# Schematic.net
KiCad netlist of a schematic drawn in Altium Designer
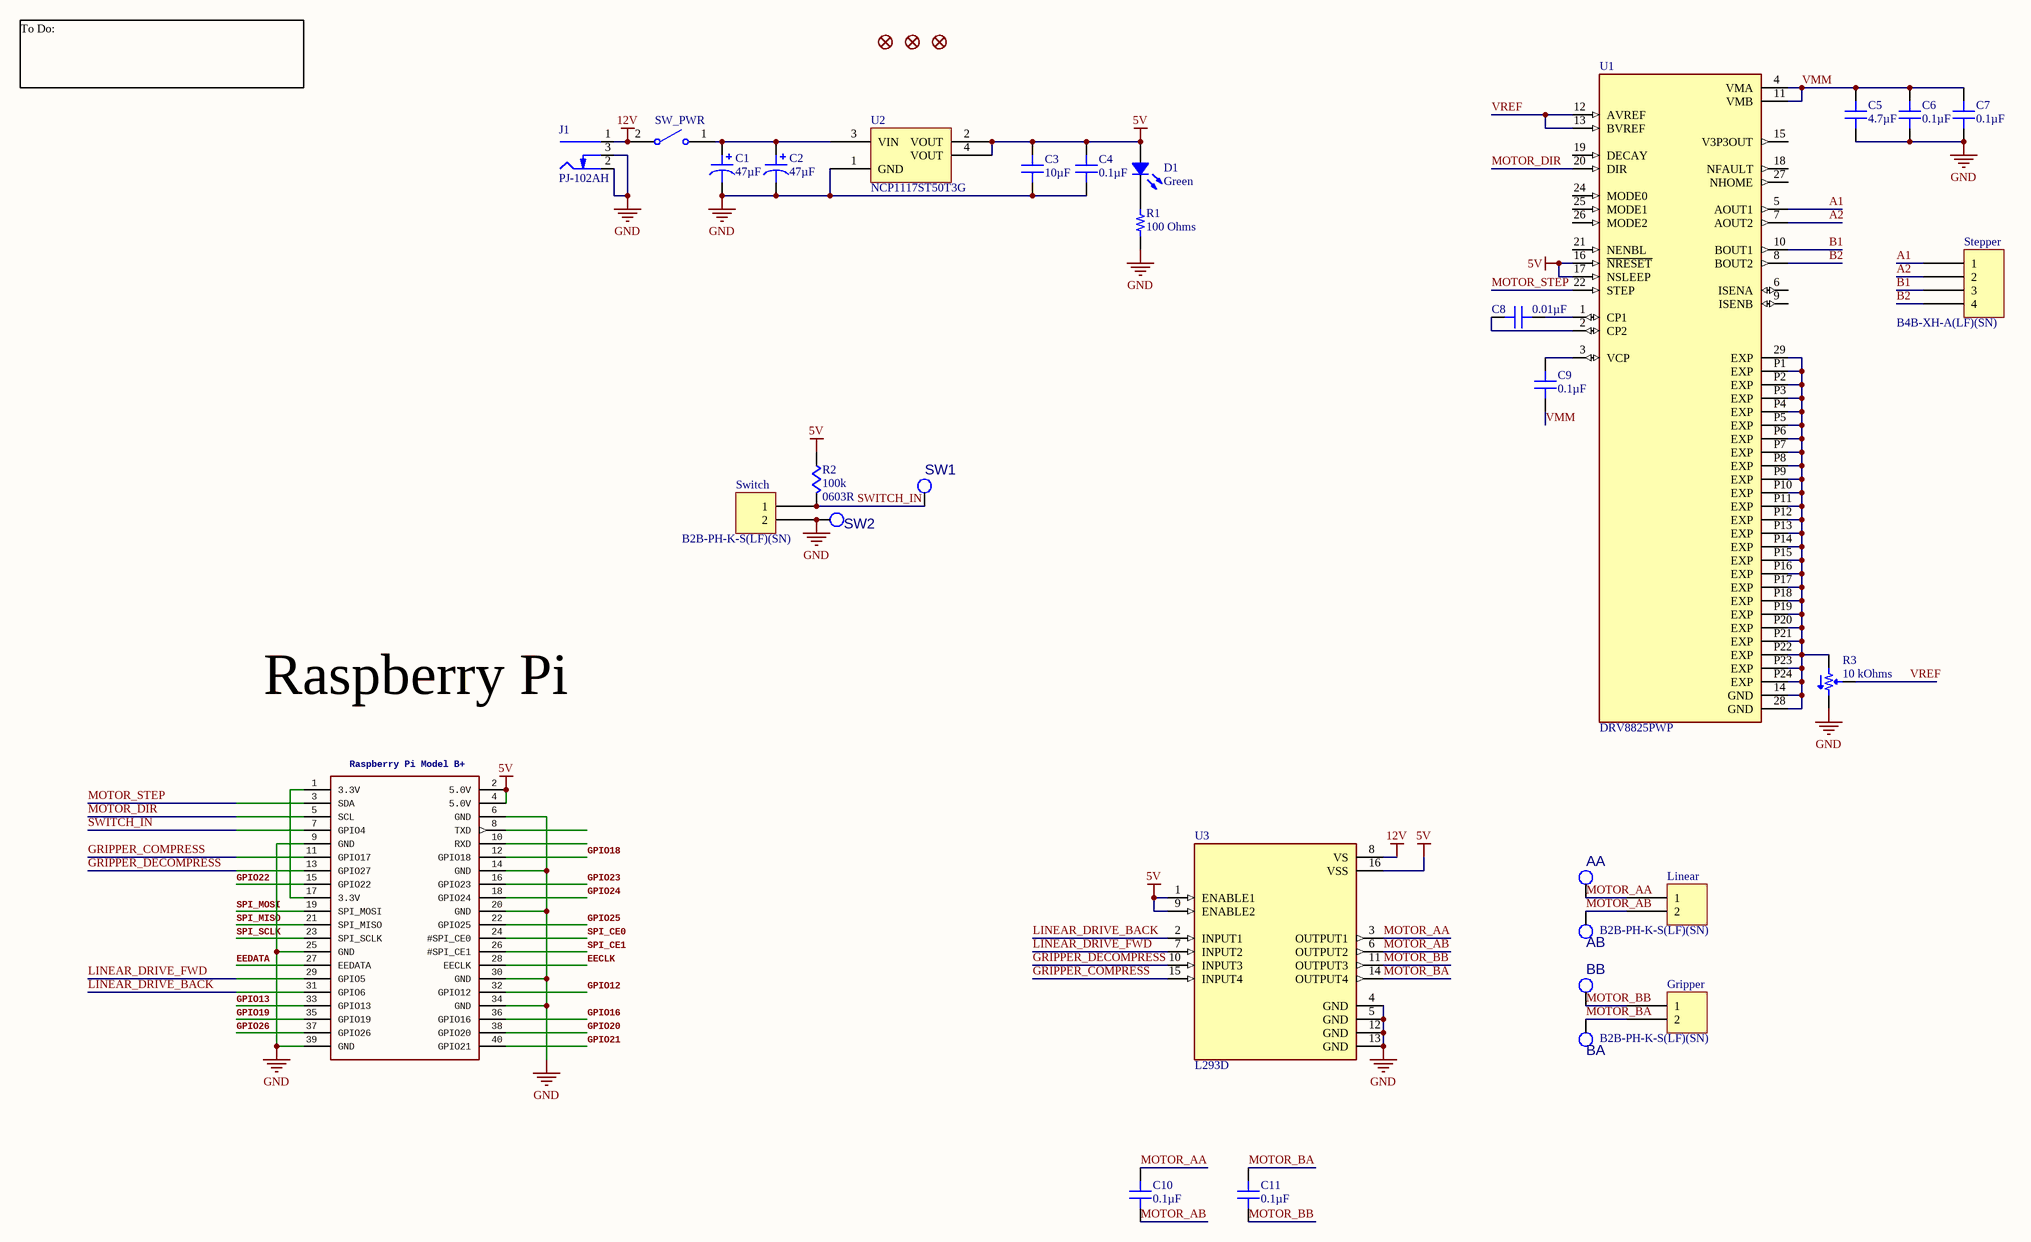
[diagram p0: Schematic.SchDoc]

(export (version "E")
  (design (tool "Eeschema 10.0.6"))
  (components
    (comp (ref "AA")
      (value "TH_Testpoint_40mil")
      (footprint "TH_Testpoint_40mil")
      (description "TH Testpoint")
      (libsource (lib "Testpoint") (part "TH_Testpoint_40mil"))
    )
    (comp (ref "AB")
      (value "TH_Testpoint_40mil")
      (footprint "TH_Testpoint_40mil")
      (description "TH Testpoint")
      (libsource (lib "Testpoint") (part "TH_Testpoint_40mil"))
    )
    (comp (ref "BA")
      (value "TH_Testpoint_40mil")
      (footprint "TH_Testpoint_40mil")
      (description "TH Testpoint")
      (libsource (lib "Testpoint") (part "TH_Testpoint_40mil"))
    )
    (comp (ref "BB")
      (value "TH_Testpoint_40mil")
      (footprint "TH_Testpoint_40mil")
      (description "TH Testpoint")
      (libsource (lib "Testpoint") (part "TH_Testpoint_40mil"))
    )
    (comp (ref "C1")
      (value "47µF")
      (footprint "CAP ALSMD 6.6MM H6.1MM")
      (description "CAP ALUM 47UF 20% 35V SMD")
      (fields (field (name "PART NUMBER") "UCD1V470MCL1GS") (field (name "MANUFACTURER") "Nichicon"))
      (libsource (lib "Celestial Altium Library - altium_library") (part "Polarised Capacitor"))
    )
    (comp (ref "C2")
      (value "47µF")
      (footprint "CAP ALSMD 6.6MM H6.1MM")
      (description "CAP ALUM 47UF 20% 35V SMD")
      (fields (field (name "PART NUMBER") "UCD1V470MCL1GS") (field (name "MANUFACTURER") "Nichicon"))
      (libsource (lib "Celestial Altium Library - altium_library") (part "Polarised Capacitor"))
    )
    (comp (ref "C3")
      (value "10µF")
      (footprint "CAP 0805_2012")
      (description "CAP CER 10UF 25V X5R 0805")
      (fields
        (field (name "PART NUMBER") "C2012X5R1E106K085AC")
        (field (name "MANUFACTURER") "TDK Corporation")
      )
      (libsource (lib "Celestial Altium Library - altium_library") (part "Capacitor"))
    )
    (comp (ref "C4")
      (value "0.1µF")
      (footprint "CAP 0603_1608")
      (description "CAP CER 0.1UF 50V X7R 0603")
      (fields
        (field (name "PART NUMBER") "CGA3E2X7R1H104K080AE")
        (field (name "MANUFACTURER") "TDK Corporation")
      )
      (libsource (lib "Celestial Altium Library - altium_library") (part "Capacitor"))
    )
    (comp (ref "C5")
      (value "4.7µF")
      (footprint "CAP 0603_1608")
      (description "CAP CER 4.7UF 35V X5R 0603")
      (fields
        (field (name "PART NUMBER") "C1608X5R1V475M080AC")
        (field (name "MANUFACTURER") "TDK Corporation")
      )
      (libsource (lib "Celestial Altium Library - altium_library") (part "Capacitor"))
    )
    (comp (ref "C6")
      (value "0.1µF")
      (footprint "CAP 0603_1608")
      (description "CAP CER 0.1UF 50V X7R 0603")
      (fields
        (field (name "PART NUMBER") "CGA3E2X7R1H104K080AE")
        (field (name "MANUFACTURER") "TDK Corporation")
      )
      (libsource (lib "Celestial Altium Library - altium_library") (part "Capacitor"))
    )
    (comp (ref "C7")
      (value "0.1µF")
      (footprint "CAP 0603_1608")
      (description "CAP CER 0.1UF 50V X7R 0603")
      (fields
        (field (name "PART NUMBER") "CGA3E2X7R1H104K080AE")
        (field (name "MANUFACTURER") "TDK Corporation")
      )
      (libsource (lib "Celestial Altium Library - altium_library") (part "Capacitor"))
    )
    (comp (ref "C8")
      (value "0.01µF")
      (footprint "CAP 0603_1608")
      (description "CAP CER 0.01UF 250V X7R 0603")
      (fields (field (name "PART NUMBER") "C0603C103KARACAUTO") (field (name "MANUFACTURER") "KEMET"))
      (libsource (lib "Celestial Altium Library - altium_library") (part "Capacitor"))
    )
    (comp (ref "C9")
      (value "0.1µF")
      (footprint "CAP 0603_1608")
      (description "CAP CER 0.1UF 50V X7R 0603")
      (fields
        (field (name "PART NUMBER") "CGA3E2X7R1H104K080AE")
        (field (name "MANUFACTURER") "TDK Corporation")
      )
      (libsource (lib "Celestial Altium Library - altium_library") (part "Capacitor"))
    )
    (comp (ref "C10")
      (value "0.1µF")
      (footprint "CAP 0603_1608")
      (description "CAP CER 0.1UF 50V X7R 0603")
      (fields
        (field (name "PART NUMBER") "CGA3E2X7R1H104K080AE")
        (field (name "MANUFACTURER") "TDK Corporation")
      )
      (libsource (lib "Celestial Altium Library - altium_library") (part "Capacitor"))
    )
    (comp (ref "C11")
      (value "0.1µF")
      (footprint "CAP 0603_1608")
      (description "CAP CER 0.1UF 50V X7R 0603")
      (fields
        (field (name "PART NUMBER") "CGA3E2X7R1H104K080AE")
        (field (name "MANUFACTURER") "TDK Corporation")
      )
      (libsource (lib "Celestial Altium Library - altium_library") (part "Capacitor"))
    )
    (comp (ref "D1")
      (value "Green")
      (footprint "LED 0603_1608 GREEN")
      (description "LED GREEN CLEAR 1608 SMD")
      (fields (field (name "PART NUMBER") "APT1608CGCK") (field (name "MANUFACTURER") "Kingbright"))
      (libsource (lib "Celestial Altium Library - altium_library") (part "LED"))
    )
    (comp (ref "FID1")
      (value "FIDUCIAL\"\"")
      (footprint "FIDUCIAL_1MM")
      (description "Fiducial Alignment PointsVarious fiducial points for machine vision alignment.")
      (libsource (lib "microbuilder") (part "FIDUCIAL{dblquote}{dblquote}"))
    )
    (comp (ref "FID2")
      (value "FIDUCIAL\"\"")
      (footprint "FIDUCIAL_1MM")
      (description "Fiducial Alignment PointsVarious fiducial points for machine vision alignment.")
      (libsource (lib "microbuilder") (part "FIDUCIAL{dblquote}{dblquote}"))
    )
    (comp (ref "FID3")
      (value "FIDUCIAL\"\"")
      (footprint "FIDUCIAL_1MM")
      (description "Fiducial Alignment PointsVarious fiducial points for machine vision alignment.")
      (libsource (lib "microbuilder") (part "FIDUCIAL{dblquote}{dblquote}"))
    )
    (comp (ref "Gripper")
      (value "B2B-PH-K-S(LF)(SN)")
      (footprint "JST B2B-PH-K")
      (description "CONN HEADER VERT 2POS 2MM")
      (fields (field (name "MANUFACTURER") "JST Sales America Inc."))
      (libsource (lib "Celestial Altium Library - altium_library") (part "2 Pin"))
    )
    (comp (ref "J1")
      (value "PJ-102AH")
      (footprint "CUI PJ-102AH")
      (description "CONN PWR JACK 2X5.5MM SOLDER")
      (fields (field (name "MANUFACTURER") "CUI Devices"))
      (libsource (lib "Celestial Altium Library - altium_library") (part "Barrel Connector"))
    )
    (comp (ref "Linear")
      (value "B2B-PH-K-S(LF)(SN)")
      (footprint "JST B2B-PH-K")
      (description "CONN HEADER VERT 2POS 2MM")
      (fields (field (name "MANUFACTURER") "JST Sales America Inc."))
      (libsource (lib "Celestial Altium Library - altium_library") (part "2 Pin"))
    )
    (comp (ref "R1")
      (value "100 Ohms")
      (footprint "RES 0603_1608")
      (description "RES 100 OHM 0.1% 1/16W 0603")
      (fields
        (field (name "PART NUMBER") "RNCS0603BKE100R")
        (field (name "MANUFACTURER") "Stackpole Electronics Inc")
      )
      (libsource (lib "Celestial Altium Library - altium_library") (part "Resistor"))
    )
    (comp (ref "R2")
      (value "100k")
      (footprint "0603R")
      (fields (field (name "Comment") "Resistor 0603"))
      (libsource (lib "MikesAltiumLibrary") (part "Resistor"))
    )
    (comp (ref "R3")
      (value "10 kOhms")
      (footprint "POT BOURNS TRIMPOT TC33")
      (description "TRIMMER 10K OHM 0.1W J LEAD TOP")
      (fields (field (name "PART NUMBER") "TC33X-2-103E") (field (name "MANUFACTURER") "Bourns Inc."))
      (libsource (lib "Celestial Altium Library - altium_library") (part "Potentiometer"))
    )
    (comp (ref "RPI1")
      (value "RASPBERRYPI_BPLUS_HATSLOTS")
      (footprint "PI_HAT_SLOTS")
      (fields (field (name "RASPBERRYPIMODELB+") "Raspberry Pi Model B+"))
      (libsource (lib "microbuilder") (part "RASPBERRYPI_BPLUS_HATSLOTS"))
    )
    (comp (ref "Stepper")
      (value "B4B-XH-A(LF)(SN)")
      (footprint "JST XH B4B-XH-A")
      (description "CONN HEADER VERT 4POS 2.5MM")
      (fields (field (name "MANUFACTURER") "JST Sales America Inc."))
      (libsource (lib "Celestial Altium Library - altium_library") (part "4 Pin"))
    )
    (comp (ref "SW1")
      (value "TH_Testpoint_40mil")
      (footprint "TH_Testpoint_40mil")
      (description "TH Testpoint")
      (libsource (lib "Testpoint") (part "TH_Testpoint_40mil"))
    )
    (comp (ref "SW2")
      (value "TH_Testpoint_40mil")
      (footprint "TH_Testpoint_40mil")
      (description "TH Testpoint")
      (libsource (lib "Testpoint") (part "TH_Testpoint_40mil"))
    )
    (comp (ref "Switch")
      (value "B2B-PH-K-S(LF)(SN)")
      (footprint "JST B2B-PH-K")
      (description "CONN HEADER VERT 2POS 2MM")
      (fields (field (name "MANUFACTURER") "JST Sales America Inc."))
      (libsource (lib "") (part "2 Pin_1"))
    )
    (comp (ref "SW_PWR")
      (value "48ASSP3S1M2QBT")
      (footprint "SWITCH SLIDE SPDT 5A 125V")
      (description "SWITCH SLIDE SPDT 5A 125V")
      (libsource (lib "MikesAltiumLibrary") (part "SWITCH SLIDE SPDT 5A 125V"))
    )
    (comp (ref "U1")
      (value "DRV8825PWP")
      (footprint "SOP65P640X120-29N")
      (description "Bipolar Motor Driver Power MOSFET Logic 28-HTSSOP")
      (fields (field (name "MF") "Texas Instruments"))
      (libsource (lib "MikesAltiumLibrary") (part "DRV8825PWP"))
    )
    (comp (ref "U2")
      (value "NCP1117ST50T3G")
      (footprint "ON SEMI SOT-223 ST(318H)")
      (description "IC REG LINEAR 5V 1A SOT223")
      (fields (field (name "MANUFACTURER") "ON Semiconductor"))
      (libsource (lib "Celestial Altium Library - altium_library") (part "ON Semi NCP1117"))
    )
    (comp (ref "U3")
      (value "L293D")
      (footprint "DIP880W50P254L2000H510Q16")
      (description "Bipolar Motor Driver Parallel 16-PowerDIP")
      (fields (field (name "MF") "STMicroelectronics"))
      (libsource (lib "MikesAltiumLibrary") (part "L293D"))
    )
  )
  (nets
    (net (code "1") (name "/A1") (class "Default")
      (node (ref "Stepper") (pin "1") (pinfunction "1_1") (pintype "passive"))
      (node (ref "U1") (pin "5") (pinfunction "AOUT1_5") (pintype "output"))
    )
    (net (code "2") (name "/A2") (class "Default")
      (node (ref "Stepper") (pin "2") (pinfunction "2_2") (pintype "passive"))
      (node (ref "U1") (pin "7") (pinfunction "AOUT2_7") (pintype "output"))
    )
    (net (code "3") (name "/B1") (class "Default")
      (node (ref "Stepper") (pin "3") (pinfunction "3_3") (pintype "passive"))
      (node (ref "U1") (pin "10") (pinfunction "BOUT1_10") (pintype "output"))
    )
    (net (code "4") (name "/B2") (class "Default")
      (node (ref "Stepper") (pin "4") (pinfunction "4_4") (pintype "passive"))
      (node (ref "U1") (pin "8") (pinfunction "BOUT2_8") (pintype "output"))
    )
    (net (code "5") (name "/EECLK") (class "Default")
      (node (ref "RPI1") (pin "28") (pinfunction "EECLK_28") (pintype "open_emitter"))
    )
    (net (code "6") (name "/EEDATA") (class "Default")
      (node (ref "RPI1") (pin "27") (pinfunction "EEDATA_27") (pintype "passive"))
    )
    (net (code "7") (name "/GPIO12") (class "Default")
      (node (ref "RPI1") (pin "32") (pinfunction "GPIO12_32") (pintype "passive"))
    )
    (net (code "8") (name "/GPIO13") (class "Default")
      (node (ref "RPI1") (pin "33") (pinfunction "GPIO13_33") (pintype "passive"))
    )
    (net (code "9") (name "/GPIO16") (class "Default")
      (node (ref "RPI1") (pin "36") (pinfunction "GPIO16_36") (pintype "open_emitter"))
    )
    (net (code "10") (name "/GPIO18") (class "Default")
      (node (ref "RPI1") (pin "12") (pinfunction "GPIO18_12") (pintype "passive"))
    )
    (net (code "11") (name "/GPIO19") (class "Default")
      (node (ref "RPI1") (pin "35") (pinfunction "GPIO19_35") (pintype "passive"))
    )
    (net (code "12") (name "/GPIO20") (class "Default")
      (node (ref "RPI1") (pin "38") (pinfunction "GPIO20_38") (pintype "passive"))
    )
    (net (code "13") (name "/GPIO21") (class "Default")
      (node (ref "RPI1") (pin "40") (pinfunction "GPIO21_40") (pintype "passive"))
    )
    (net (code "14") (name "/GPIO22") (class "Default")
      (node (ref "RPI1") (pin "15") (pinfunction "GPIO22_15") (pintype "passive"))
    )
    (net (code "15") (name "/GPIO23") (class "Default")
      (node (ref "RPI1") (pin "16") (pinfunction "GPIO23_16") (pintype "passive"))
    )
    (net (code "16") (name "/GPIO24") (class "Default")
      (node (ref "RPI1") (pin "18") (pinfunction "GPIO24_18") (pintype "passive"))
    )
    (net (code "17") (name "/GPIO25") (class "Default")
      (node (ref "RPI1") (pin "22") (pinfunction "GPIO25_22") (pintype "passive"))
    )
    (net (code "18") (name "/GPIO26") (class "Default")
      (node (ref "RPI1") (pin "37") (pinfunction "GPIO26_37") (pintype "passive"))
    )
    (net (code "19") (name "/GRIPPER_COMPRESS") (class "Default")
      (node (ref "RPI1") (pin "11") (pinfunction "GPIO17_11") (pintype "passive"))
      (node (ref "U3") (pin "15") (pinfunction "INPUT4_15") (pintype "input"))
    )
    (net (code "20") (name "/GRIPPER_DECOMPRESS") (class "Default")
      (node (ref "RPI1") (pin "13") (pinfunction "GPIO27_13") (pintype "passive"))
      (node (ref "U3") (pin "10") (pinfunction "INPUT3_10") (pintype "input"))
    )
    (net (code "21") (name "/LINEAR_DRIVE_BACK") (class "Default")
      (node (ref "RPI1") (pin "31") (pinfunction "GPIO6_31") (pintype "open_emitter"))
      (node (ref "U3") (pin "2") (pinfunction "INPUT1_2") (pintype "input"))
    )
    (net (code "22") (name "/LINEAR_DRIVE_FWD") (class "Default")
      (node (ref "RPI1") (pin "29") (pinfunction "GPIO5_29") (pintype "passive"))
      (node (ref "U3") (pin "7") (pinfunction "INPUT2_7") (pintype "input"))
    )
    (net (code "23") (name "/MOTOR_AA") (class "Default")
      (node (ref "AA") (pin "1") (pinfunction "1_1") (pintype "passive"))
      (node (ref "C10") (pin "2") (pinfunction "2_2") (pintype "passive"))
      (node (ref "Linear") (pin "1") (pinfunction "1_1") (pintype "passive"))
      (node (ref "U3") (pin "3") (pinfunction "OUTPUT1_3") (pintype "output"))
    )
    (net (code "24") (name "/MOTOR_AB") (class "Default")
      (node (ref "AB") (pin "1") (pinfunction "1_1") (pintype "passive"))
      (node (ref "C10") (pin "1") (pinfunction "1_1") (pintype "passive"))
      (node (ref "Linear") (pin "2") (pinfunction "2_2") (pintype "passive"))
      (node (ref "U3") (pin "6") (pinfunction "OUTPUT2_6") (pintype "output"))
    )
    (net (code "25") (name "/MOTOR_BA") (class "Default")
      (node (ref "BA") (pin "1") (pinfunction "1_1") (pintype "passive"))
      (node (ref "C11") (pin "2") (pinfunction "2_2") (pintype "passive"))
      (node (ref "Gripper") (pin "2") (pinfunction "2_2") (pintype "passive"))
      (node (ref "U3") (pin "14") (pinfunction "OUTPUT4_14") (pintype "output"))
    )
    (net (code "26") (name "/MOTOR_BB") (class "Default")
      (node (ref "BB") (pin "1") (pinfunction "1_1") (pintype "passive"))
      (node (ref "C11") (pin "1") (pinfunction "1_1") (pintype "passive"))
      (node (ref "Gripper") (pin "1") (pinfunction "1_1") (pintype "passive"))
      (node (ref "U3") (pin "11") (pinfunction "OUTPUT3_11") (pintype "output"))
    )
    (net (code "27") (name "/MOTOR_DIR") (class "Default")
      (node (ref "RPI1") (pin "5") (pinfunction "SCL_5") (pintype "passive"))
      (node (ref "U1") (pin "20") (pinfunction "DIR_20") (pintype "input"))
    )
    (net (code "28") (name "/MOTOR_STEP") (class "Default")
      (node (ref "RPI1") (pin "3") (pinfunction "SDA_3") (pintype "passive"))
      (node (ref "U1") (pin "22") (pinfunction "STEP_22") (pintype "input"))
    )
    (net (code "29") (name "/SPI_CE0") (class "Default")
      (node (ref "RPI1") (pin "24") (pinfunction "#SPI_CE0_24") (pintype "passive"))
    )
    (net (code "30") (name "/SPI_CE1") (class "Default")
      (node (ref "RPI1") (pin "26") (pinfunction "#SPI_CE1_26") (pintype "passive"))
    )
    (net (code "31") (name "/SPI_MISO") (class "Default")
      (node (ref "RPI1") (pin "21") (pinfunction "SPI_MISO_21") (pintype "passive"))
    )
    (net (code "32") (name "/SPI_MOSI") (class "Default")
      (node (ref "RPI1") (pin "19") (pinfunction "SPI_MOSI_19") (pintype "passive"))
    )
    (net (code "33") (name "/SPI_SCLK") (class "Default")
      (node (ref "RPI1") (pin "23") (pinfunction "SPI_SCLK_23") (pintype "passive"))
    )
    (net (code "34") (name "/SWITCH_IN") (class "Default")
      (node (ref "R2") (pin "1") (pinfunction "1_1") (pintype "power_in"))
      (node (ref "RPI1") (pin "7") (pinfunction "GPIO4_7") (pintype "passive"))
      (node (ref "SW1") (pin "1") (pinfunction "1_1") (pintype "passive"))
      (node (ref "Switch") (pin "1") (pinfunction "1_1") (pintype "passive"))
    )
    (net (code "35") (name "/VMM") (class "Default")
      (node (ref "C5") (pin "2") (pinfunction "2_2") (pintype "passive"))
      (node (ref "C6") (pin "2") (pinfunction "2_2") (pintype "passive"))
      (node (ref "C7") (pin "2") (pinfunction "2_2") (pintype "passive"))
      (node (ref "C9") (pin "1") (pinfunction "1_1") (pintype "passive"))
      (node (ref "U1") (pin "11") (pinfunction "VMB_11") (pintype "power_in"))
      (node (ref "U1") (pin "4") (pinfunction "VMA_4") (pintype "power_in"))
    )
    (net (code "36") (name "/VREF") (class "Default")
      (node (ref "R3") (pin "2") (pinfunction "2_2") (pintype "passive"))
      (node (ref "U1") (pin "12") (pinfunction "AVREF_12") (pintype "input"))
      (node (ref "U1") (pin "13") (pinfunction "BVREF_13") (pintype "input"))
    )
    (net (code "37") (name "5V") (class "Default")
      (node (ref "C3") (pin "2") (pinfunction "2_2") (pintype "passive"))
      (node (ref "C4") (pin "2") (pinfunction "2_2") (pintype "passive"))
      (node (ref "D1") (pin "1") (pinfunction "1_1") (pintype "passive"))
      (node (ref "R2") (pin "2") (pinfunction "2_2") (pintype "power_in"))
      (node (ref "RPI1") (pin "2") (pinfunction "5.0V_2") (pintype "open_emitter"))
      (node (ref "RPI1") (pin "4") (pinfunction "5.0V_4") (pintype "open_emitter"))
      (node (ref "U1") (pin "16") (pinfunction "~{NRESET}_16") (pintype "input"))
      (node (ref "U1") (pin "17") (pinfunction "NSLEEP_17") (pintype "input"))
      (node (ref "U2") (pin "2") (pinfunction "VOUT_2") (pintype "passive"))
      (node (ref "U2") (pin "4") (pinfunction "VOUT_4") (pintype "passive"))
      (node (ref "U3") (pin "1") (pinfunction "ENABLE1_1") (pintype "input"))
      (node (ref "U3") (pin "16") (pinfunction "VSS_16") (pintype "power_in"))
      (node (ref "U3") (pin "9") (pinfunction "ENABLE2_9") (pintype "input"))
    )
    (net (code "38") (name "12V") (class "Default")
      (node (ref "J1") (pin "1") (pinfunction "Centre_1") (pintype "passive"))
      (node (ref "SW_PWR") (pin "2") (pinfunction "2_2") (pintype "passive"))
      (node (ref "U3") (pin "8") (pinfunction "VS_8") (pintype "power_in"))
    )
    (net (code "39") (name "GND") (class "Default")
      (node (ref "C1") (pin "2") (pinfunction "2_2") (pintype "passive"))
      (node (ref "C2") (pin "2") (pinfunction "2_2") (pintype "passive"))
      (node (ref "C3") (pin "1") (pinfunction "1_1") (pintype "passive"))
      (node (ref "C4") (pin "1") (pinfunction "1_1") (pintype "passive"))
      (node (ref "C5") (pin "1") (pinfunction "1_1") (pintype "passive"))
      (node (ref "C6") (pin "1") (pinfunction "1_1") (pintype "passive"))
      (node (ref "C7") (pin "1") (pinfunction "1_1") (pintype "passive"))
      (node (ref "J1") (pin "2") (pinfunction "Outer_2") (pintype "passive"))
      (node (ref "J1") (pin "3") (pinfunction "SW_3") (pintype "passive"))
      (node (ref "R1") (pin "1") (pinfunction "1_1") (pintype "passive"))
      (node (ref "R3") (pin "3") (pinfunction "3_3") (pintype "passive"))
      (node (ref "RPI1") (pin "14") (pinfunction "GND_14") (pintype "open_emitter"))
      (node (ref "RPI1") (pin "20") (pinfunction "GND_20") (pintype "open_emitter"))
      (node (ref "RPI1") (pin "25") (pinfunction "GND_25") (pintype "open_emitter"))
      (node (ref "RPI1") (pin "30") (pinfunction "GND_30") (pintype "passive"))
      (node (ref "RPI1") (pin "34") (pinfunction "GND_34") (pintype "passive"))
      (node (ref "RPI1") (pin "39") (pinfunction "GND_39") (pintype "open_emitter"))
      (node (ref "RPI1") (pin "6") (pinfunction "GND_6") (pintype "open_emitter"))
      (node (ref "RPI1") (pin "9") (pinfunction "GND_9") (pintype "open_emitter"))
      (node (ref "SW2") (pin "1") (pinfunction "1_1") (pintype "passive"))
      (node (ref "Switch") (pin "2") (pinfunction "2_2") (pintype "passive"))
      (node (ref "U2") (pin "1") (pinfunction "GND_1") (pintype "passive"))
      (node (ref "U3") (pin "12") (pinfunction "GND_12") (pintype "power_in"))
      (node (ref "U3") (pin "13") (pinfunction "GND_13") (pintype "power_in"))
      (node (ref "U3") (pin "4") (pinfunction "GND_4") (pintype "power_in"))
      (node (ref "U3") (pin "5") (pinfunction "GND_5") (pintype "power_in"))
    )
    (net (code "40") (name "Net-(D1-Pad2)") (class "Default")
      (node (ref "D1") (pin "2") (pinfunction "2_2") (pintype "passive"))
      (node (ref "R1") (pin "2") (pinfunction "2_2") (pintype "passive"))
    )
    (net (code "41") (name "Net-(R3-Pad1)") (class "Default")
      (node (ref "R3") (pin "1") (pinfunction "1_1") (pintype "passive"))
      (node (ref "U1") (pin "14") (pinfunction "GND_14") (pintype "power_in"))
      (node (ref "U1") (pin "28") (pinfunction "GND_28") (pintype "power_in"))
      (node (ref "U1") (pin "29") (pinfunction "EXP_29") (pintype "power_in"))
      (node (ref "U1") (pin "P1") (pinfunction "EXP_P1") (pintype "power_in"))
      (node (ref "U1") (pin "P10") (pinfunction "EXP_P10") (pintype "power_in"))
      (node (ref "U1") (pin "P11") (pinfunction "EXP_P11") (pintype "power_in"))
      (node (ref "U1") (pin "P12") (pinfunction "EXP_P12") (pintype "power_in"))
      (node (ref "U1") (pin "P13") (pinfunction "EXP_P13") (pintype "power_in"))
      (node (ref "U1") (pin "P14") (pinfunction "EXP_P14") (pintype "power_in"))
      (node (ref "U1") (pin "P15") (pinfunction "EXP_P15") (pintype "power_in"))
      (node (ref "U1") (pin "P16") (pinfunction "EXP_P16") (pintype "power_in"))
      (node (ref "U1") (pin "P17") (pinfunction "EXP_P17") (pintype "power_in"))
      (node (ref "U1") (pin "P18") (pinfunction "EXP_P18") (pintype "power_in"))
      (node (ref "U1") (pin "P19") (pinfunction "EXP_P19") (pintype "power_in"))
      (node (ref "U1") (pin "P2") (pinfunction "EXP_P2") (pintype "power_in"))
      (node (ref "U1") (pin "P20") (pinfunction "EXP_P20") (pintype "power_in"))
      (node (ref "U1") (pin "P21") (pinfunction "EXP_P21") (pintype "power_in"))
      (node (ref "U1") (pin "P22") (pinfunction "EXP_P22") (pintype "power_in"))
      (node (ref "U1") (pin "P23") (pinfunction "EXP_P23") (pintype "power_in"))
      (node (ref "U1") (pin "P24") (pinfunction "EXP_P24") (pintype "power_in"))
      (node (ref "U1") (pin "P3") (pinfunction "EXP_P3") (pintype "power_in"))
      (node (ref "U1") (pin "P4") (pinfunction "EXP_P4") (pintype "power_in"))
      (node (ref "U1") (pin "P5") (pinfunction "EXP_P5") (pintype "power_in"))
      (node (ref "U1") (pin "P6") (pinfunction "EXP_P6") (pintype "power_in"))
      (node (ref "U1") (pin "P7") (pinfunction "EXP_P7") (pintype "power_in"))
      (node (ref "U1") (pin "P8") (pinfunction "EXP_P8") (pintype "power_in"))
      (node (ref "U1") (pin "P9") (pinfunction "EXP_P9") (pintype "power_in"))
    )
    (net (code "42") (name "Net-(RPI1-3.3V-Pad1)") (class "Default")
      (node (ref "RPI1") (pin "1") (pinfunction "3.3V_1") (pintype "open_emitter"))
      (node (ref "RPI1") (pin "17") (pinfunction "3.3V_17") (pintype "open_emitter"))
    )
    (net (code "43") (name "Net-(U1-CP1)") (class "Default")
      (node (ref "C8") (pin "2") (pinfunction "2_2") (pintype "passive"))
      (node (ref "U1") (pin "1") (pinfunction "CP1_1") (pintype "bidirectional"))
    )
    (net (code "44") (name "Net-(U1-CP2)") (class "Default")
      (node (ref "C8") (pin "1") (pinfunction "1_1") (pintype "passive"))
      (node (ref "U1") (pin "2") (pinfunction "CP2_2") (pintype "bidirectional"))
    )
    (net (code "45") (name "Net-(U1-VCP)") (class "Default")
      (node (ref "C9") (pin "2") (pinfunction "2_2") (pintype "passive"))
      (node (ref "U1") (pin "3") (pinfunction "VCP_3") (pintype "bidirectional"))
    )
    (net (code "46") (name "Net-(U2-VIN)") (class "Default")
      (node (ref "C1") (pin "1") (pinfunction "1_1") (pintype "passive"))
      (node (ref "C2") (pin "1") (pinfunction "1_1") (pintype "passive"))
      (node (ref "SW_PWR") (pin "1") (pinfunction "1_1") (pintype "passive"))
      (node (ref "U2") (pin "3") (pinfunction "VIN_3") (pintype "passive"))
    )
    (net (code "47") (name "unconnected-(RPI1-RXD-Pad10)") (class "Default")
      (node (ref "RPI1") (pin "10") (pinfunction "RXD_10") (pintype "passive"))
    )
    (net (code "48") (name "unconnected-(RPI1-TXD-Pad8)") (class "Default")
      (node (ref "RPI1") (pin "8") (pinfunction "TXD_8") (pintype "output"))
    )
    (net (code "49") (name "unconnected-(U1-DECAY-Pad19)") (class "Default")
      (node (ref "U1") (pin "19") (pinfunction "DECAY_19") (pintype "input"))
    )
    (net (code "50") (name "unconnected-(U1-ISENA-Pad6)") (class "Default")
      (node (ref "U1") (pin "6") (pinfunction "ISENA_6") (pintype "bidirectional"))
    )
    (net (code "51") (name "unconnected-(U1-ISENB-Pad9)") (class "Default")
      (node (ref "U1") (pin "9") (pinfunction "ISENB_9") (pintype "bidirectional"))
    )
    (net (code "52") (name "unconnected-(U1-MODE0-Pad24)") (class "Default")
      (node (ref "U1") (pin "24") (pinfunction "MODE0_24") (pintype "input"))
    )
    (net (code "53") (name "unconnected-(U1-MODE1-Pad25)") (class "Default")
      (node (ref "U1") (pin "25") (pinfunction "MODE1_25") (pintype "input"))
    )
    (net (code "54") (name "unconnected-(U1-MODE2-Pad26)") (class "Default")
      (node (ref "U1") (pin "26") (pinfunction "MODE2_26") (pintype "input"))
    )
    (net (code "55") (name "unconnected-(U1-NENBL-Pad21)") (class "Default")
      (node (ref "U1") (pin "21") (pinfunction "NENBL_21") (pintype "input"))
    )
    (net (code "56") (name "unconnected-(U1-NFAULT-Pad18)") (class "Default")
      (node (ref "U1") (pin "18") (pinfunction "NFAULT_18") (pintype "output"))
    )
    (net (code "57") (name "unconnected-(U1-NHOME-Pad27)") (class "Default")
      (node (ref "U1") (pin "27") (pinfunction "NHOME_27") (pintype "output"))
    )
    (net (code "58") (name "unconnected-(U1-V3P3OUT-Pad15)") (class "Default")
      (node (ref "U1") (pin "15") (pinfunction "V3P3OUT_15") (pintype "output"))
    )
  )
)
